# Sheet1.net
KiCad netlist of a schematic drawn in Altium Designer
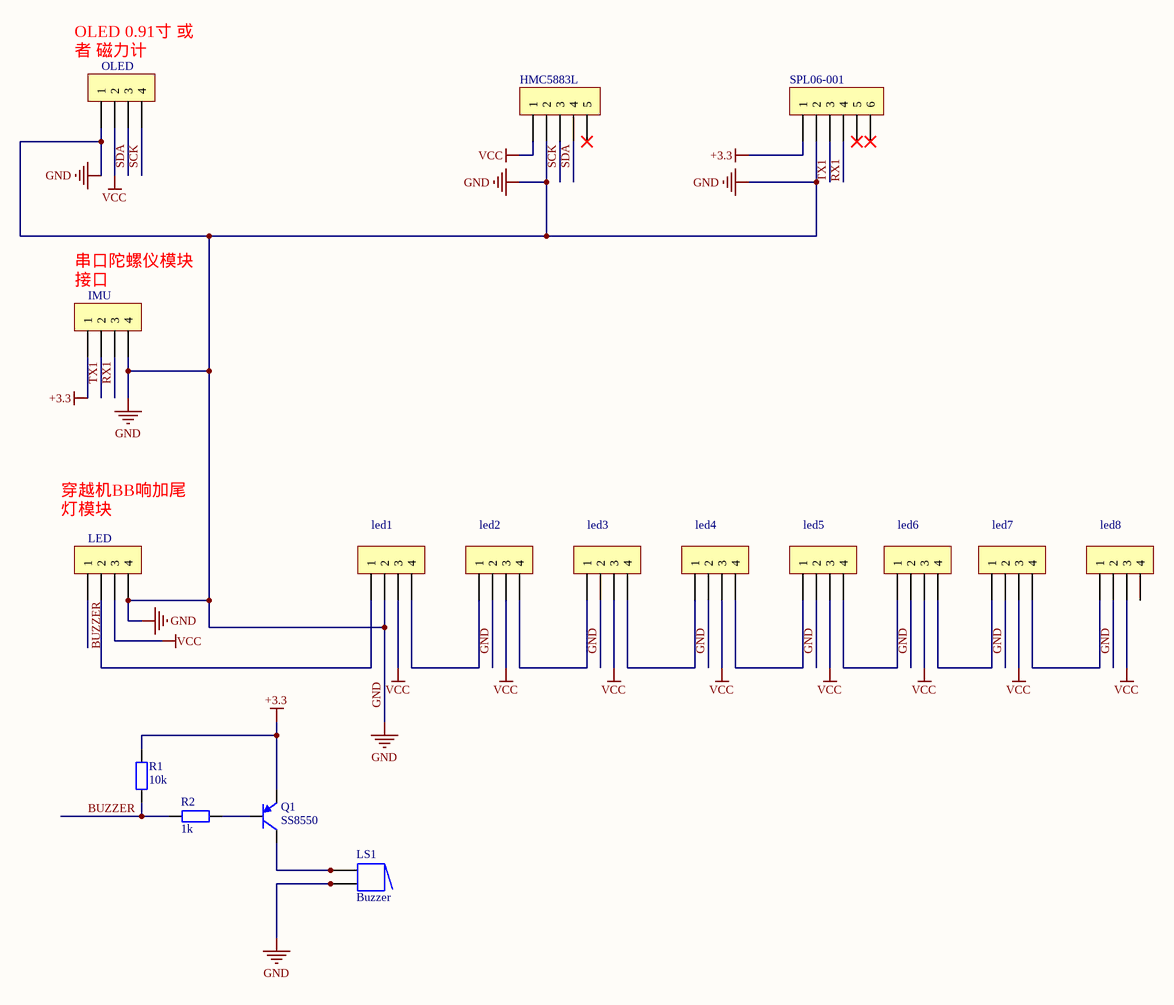
[diagram p0: Sheet1.SchDoc]

(export (version "E")
  (design (tool "Eeschema 10.0.6"))
  (components
    (comp (ref "HMC5883L")
      (value "Pin HDR1X5")
      (footprint "Pin HDR1X5/2.54mm-S")
      (libsource (lib "排针") (part "Pin HDR1X5"))
    )
    (comp (ref "IMU")
      (value "Female HDR1X4")
      (footprint "SH1.0 S-W-4P")
      (libsource (lib "排母") (part "Female HDR1X4"))
    )
    (comp (ref "LED")
      (value "Female HDR1X4")
      (footprint "SH1.0 S-W-4P")
      (libsource (lib "排母") (part "Female HDR1X4"))
    )
    (comp (ref "led1")
      (value "Pin HDR1X4")
      (footprint "SH1.0 S-W-4P")
      (libsource (lib "排针") (part "Pin HDR1X4"))
    )
    (comp (ref "led2")
      (value "Pin HDR1X4")
      (footprint "SH1.0 S-W-4P")
      (libsource (lib "排针") (part "Pin HDR1X4"))
    )
    (comp (ref "led3")
      (value "Pin HDR1X4")
      (footprint "SH1.0 S-W-4P")
      (libsource (lib "排针") (part "Pin HDR1X4"))
    )
    (comp (ref "led4")
      (value "Pin HDR1X4")
      (footprint "SH1.0 S-W-4P")
      (libsource (lib "排针") (part "Pin HDR1X4"))
    )
    (comp (ref "led5")
      (value "Pin HDR1X4")
      (footprint "SH1.0 S-W-4P")
      (libsource (lib "排针") (part "Pin HDR1X4"))
    )
    (comp (ref "led6")
      (value "Pin HDR1X4")
      (footprint "SH1.0 S-W-4P")
      (libsource (lib "排针") (part "Pin HDR1X4"))
    )
    (comp (ref "led7")
      (value "Pin HDR1X4")
      (footprint "SH1.0 S-W-4P")
      (libsource (lib "排针") (part "Pin HDR1X4"))
    )
    (comp (ref "led8")
      (value "Pin HDR1X4")
      (footprint "SH1.0 S-W-4P")
      (libsource (lib "排针") (part "Pin HDR1X4"))
    )
    (comp (ref "LS1")
      (value "Buzzer")
      (footprint "Buzzer")
      (description "Magnetic Transducer Buzzer")
      (fields (field (name "PUBLISHER") "Altium Limited"))
      (libsource (lib "Miscellaneous Devices") (part "Buzzer"))
    )
    (comp (ref "OLED")
      (value "Female HDR1X4")
      (footprint "SH1.0 S-W-4P")
      (libsource (lib "排母") (part "Female HDR1X4"))
    )
    (comp (ref "Q1")
      (value "SS8550")
      (footprint "SOT23-3N")
      (description "低频放大-PNP型")
      (fields (field (name "版权归属") "源创客"))
      (libsource (lib "三极管B") (part "9012-SMD"))
    )
    (comp (ref "R1")
      (value "10k")
      (footprint "R 0603_M")
      (description "贴片电阻")
      (fields (field (name "版权归属") "源创客"))
      (libsource (lib "3.1   - 电阻-电容-电感") (part "R"))
    )
    (comp (ref "R2")
      (value "1k")
      (footprint "R 0603_M")
      (description "贴片电阻")
      (fields (field (name "版权归属") "源创客"))
      (libsource (lib "3.1   - 电阻-电容-电感") (part "R"))
    )
    (comp (ref "SPL06-001")
      (value "Pin HDR1X6")
      (footprint "Pin HDR1X6/2.54mm-S")
      (libsource (lib "排针") (part "Pin HDR1X6"))
    )
  )
  (nets
    (net (code "1") (name "+3.3") (class "Default")
      (node (ref "IMU") (pin "1") (pinfunction "1_1") (pintype "passive"))
      (node (ref "Q1") (pin "2") (pinfunction "E_2") (pintype "passive"))
      (node (ref "R1") (pin "2") (pinfunction "2_2") (pintype "passive"))
      (node (ref "SPL06-001") (pin "1") (pinfunction "1_1") (pintype "passive"))
    )
    (net (code "2") (name "/BUZZER") (class "Default")
      (node (ref "LED") (pin "1") (pinfunction "1_1") (pintype "passive"))
      (node (ref "R1") (pin "1") (pinfunction "1_1") (pintype "passive"))
      (node (ref "R2") (pin "2") (pinfunction "2_2") (pintype "passive"))
    )
    (net (code "3") (name "/RX1") (class "Default")
      (node (ref "IMU") (pin "3") (pinfunction "3_3") (pintype "passive"))
      (node (ref "SPL06-001") (pin "4") (pinfunction "4_4") (pintype "passive"))
    )
    (net (code "4") (name "/SCK") (class "Default")
      (node (ref "HMC5883L") (pin "3") (pinfunction "3_3") (pintype "passive"))
      (node (ref "OLED") (pin "4") (pinfunction "4_4") (pintype "passive"))
    )
    (net (code "5") (name "/SDA") (class "Default")
      (node (ref "HMC5883L") (pin "4") (pinfunction "4_4") (pintype "passive"))
      (node (ref "OLED") (pin "3") (pinfunction "3_3") (pintype "passive"))
    )
    (net (code "6") (name "/TX1") (class "Default")
      (node (ref "IMU") (pin "2") (pinfunction "2_2") (pintype "passive"))
      (node (ref "SPL06-001") (pin "3") (pinfunction "3_3") (pintype "passive"))
    )
    (net (code "7") (name "GND") (class "Default")
      (node (ref "HMC5883L") (pin "2") (pinfunction "2_2") (pintype "passive"))
      (node (ref "IMU") (pin "4") (pinfunction "4_4") (pintype "passive"))
      (node (ref "LED") (pin "4") (pinfunction "4_4") (pintype "passive"))
      (node (ref "LS1") (pin "2") (pinfunction "2_2") (pintype "passive"))
      (node (ref "LS1") (pin "2A") (pinfunction "2A_2A") (pintype "passive"))
      (node (ref "OLED") (pin "1") (pinfunction "1_1") (pintype "passive"))
      (node (ref "SPL06-001") (pin "2") (pinfunction "2_2") (pintype "passive"))
      (node (ref "led1") (pin "2") (pinfunction "2_2") (pintype "passive"))
      (node (ref "led2") (pin "2") (pinfunction "2_2") (pintype "passive"))
      (node (ref "led3") (pin "2") (pinfunction "2_2") (pintype "passive"))
      (node (ref "led4") (pin "2") (pinfunction "2_2") (pintype "passive"))
      (node (ref "led5") (pin "2") (pinfunction "2_2") (pintype "passive"))
      (node (ref "led6") (pin "2") (pinfunction "2_2") (pintype "passive"))
      (node (ref "led7") (pin "2") (pinfunction "2_2") (pintype "passive"))
      (node (ref "led8") (pin "2") (pinfunction "2_2") (pintype "passive"))
    )
    (net (code "8") (name "Net-(LED-Pad2)") (class "Default")
      (node (ref "LED") (pin "2") (pinfunction "2_2") (pintype "passive"))
      (node (ref "led1") (pin "1") (pinfunction "1_1") (pintype "passive"))
    )
    (net (code "9") (name "Net-(Q1-B)") (class "Default")
      (node (ref "Q1") (pin "1") (pinfunction "B_1") (pintype "passive"))
      (node (ref "R2") (pin "1") (pinfunction "1_1") (pintype "passive"))
    )
    (net (code "10") (name "Net-(Q1-C)") (class "Default")
      (node (ref "LS1") (pin "1") (pinfunction "1_1") (pintype "passive"))
      (node (ref "LS1") (pin "1A") (pinfunction "1A_1A") (pintype "passive"))
      (node (ref "Q1") (pin "3") (pinfunction "C_3") (pintype "passive"))
    )
    (net (code "11") (name "Net-(led1-Pad4)") (class "Default")
      (node (ref "led1") (pin "4") (pinfunction "4_4") (pintype "passive"))
      (node (ref "led2") (pin "1") (pinfunction "1_1") (pintype "passive"))
    )
    (net (code "12") (name "Net-(led2-Pad4)") (class "Default")
      (node (ref "led2") (pin "4") (pinfunction "4_4") (pintype "passive"))
      (node (ref "led3") (pin "1") (pinfunction "1_1") (pintype "passive"))
    )
    (net (code "13") (name "Net-(led3-Pad4)") (class "Default")
      (node (ref "led3") (pin "4") (pinfunction "4_4") (pintype "passive"))
      (node (ref "led4") (pin "1") (pinfunction "1_1") (pintype "passive"))
    )
    (net (code "14") (name "Net-(led4-Pad4)") (class "Default")
      (node (ref "led4") (pin "4") (pinfunction "4_4") (pintype "passive"))
      (node (ref "led5") (pin "1") (pinfunction "1_1") (pintype "passive"))
    )
    (net (code "15") (name "Net-(led5-Pad4)") (class "Default")
      (node (ref "led5") (pin "4") (pinfunction "4_4") (pintype "passive"))
      (node (ref "led6") (pin "1") (pinfunction "1_1") (pintype "passive"))
    )
    (net (code "16") (name "Net-(led6-Pad4)") (class "Default")
      (node (ref "led6") (pin "4") (pinfunction "4_4") (pintype "passive"))
      (node (ref "led7") (pin "1") (pinfunction "1_1") (pintype "passive"))
    )
    (net (code "17") (name "Net-(led7-Pad4)") (class "Default")
      (node (ref "led7") (pin "4") (pinfunction "4_4") (pintype "passive"))
      (node (ref "led8") (pin "1") (pinfunction "1_1") (pintype "passive"))
    )
    (net (code "18") (name "VCC") (class "Default")
      (node (ref "HMC5883L") (pin "1") (pinfunction "1_1") (pintype "passive"))
      (node (ref "LED") (pin "3") (pinfunction "3_3") (pintype "passive"))
      (node (ref "OLED") (pin "2") (pinfunction "2_2") (pintype "passive"))
      (node (ref "led1") (pin "3") (pinfunction "3_3") (pintype "passive"))
      (node (ref "led2") (pin "3") (pinfunction "3_3") (pintype "passive"))
      (node (ref "led3") (pin "3") (pinfunction "3_3") (pintype "passive"))
      (node (ref "led4") (pin "3") (pinfunction "3_3") (pintype "passive"))
      (node (ref "led5") (pin "3") (pinfunction "3_3") (pintype "passive"))
      (node (ref "led6") (pin "3") (pinfunction "3_3") (pintype "passive"))
      (node (ref "led7") (pin "3") (pinfunction "3_3") (pintype "passive"))
      (node (ref "led8") (pin "3") (pinfunction "3_3") (pintype "passive"))
    )
    (net (code "19") (name "unconnected-(HMC5883L-Pad5)") (class "Default")
      (node (ref "HMC5883L") (pin "5") (pinfunction "5_5") (pintype "passive+no_connect"))
    )
    (net (code "20") (name "unconnected-(SPL06-001-Pad5)") (class "Default")
      (node (ref "SPL06-001") (pin "5") (pinfunction "5_5") (pintype "passive+no_connect"))
    )
    (net (code "21") (name "unconnected-(SPL06-001-Pad6)") (class "Default")
      (node (ref "SPL06-001") (pin "6") (pinfunction "6_6") (pintype "passive+no_connect"))
    )
    (net (code "22") (name "unconnected-(led8-Pad4)") (class "Default")
      (node (ref "led8") (pin "4") (pinfunction "4_4") (pintype "passive"))
    )
  )
)
